# SFP.net
KiCad netlist of a schematic drawn in Altium Designer
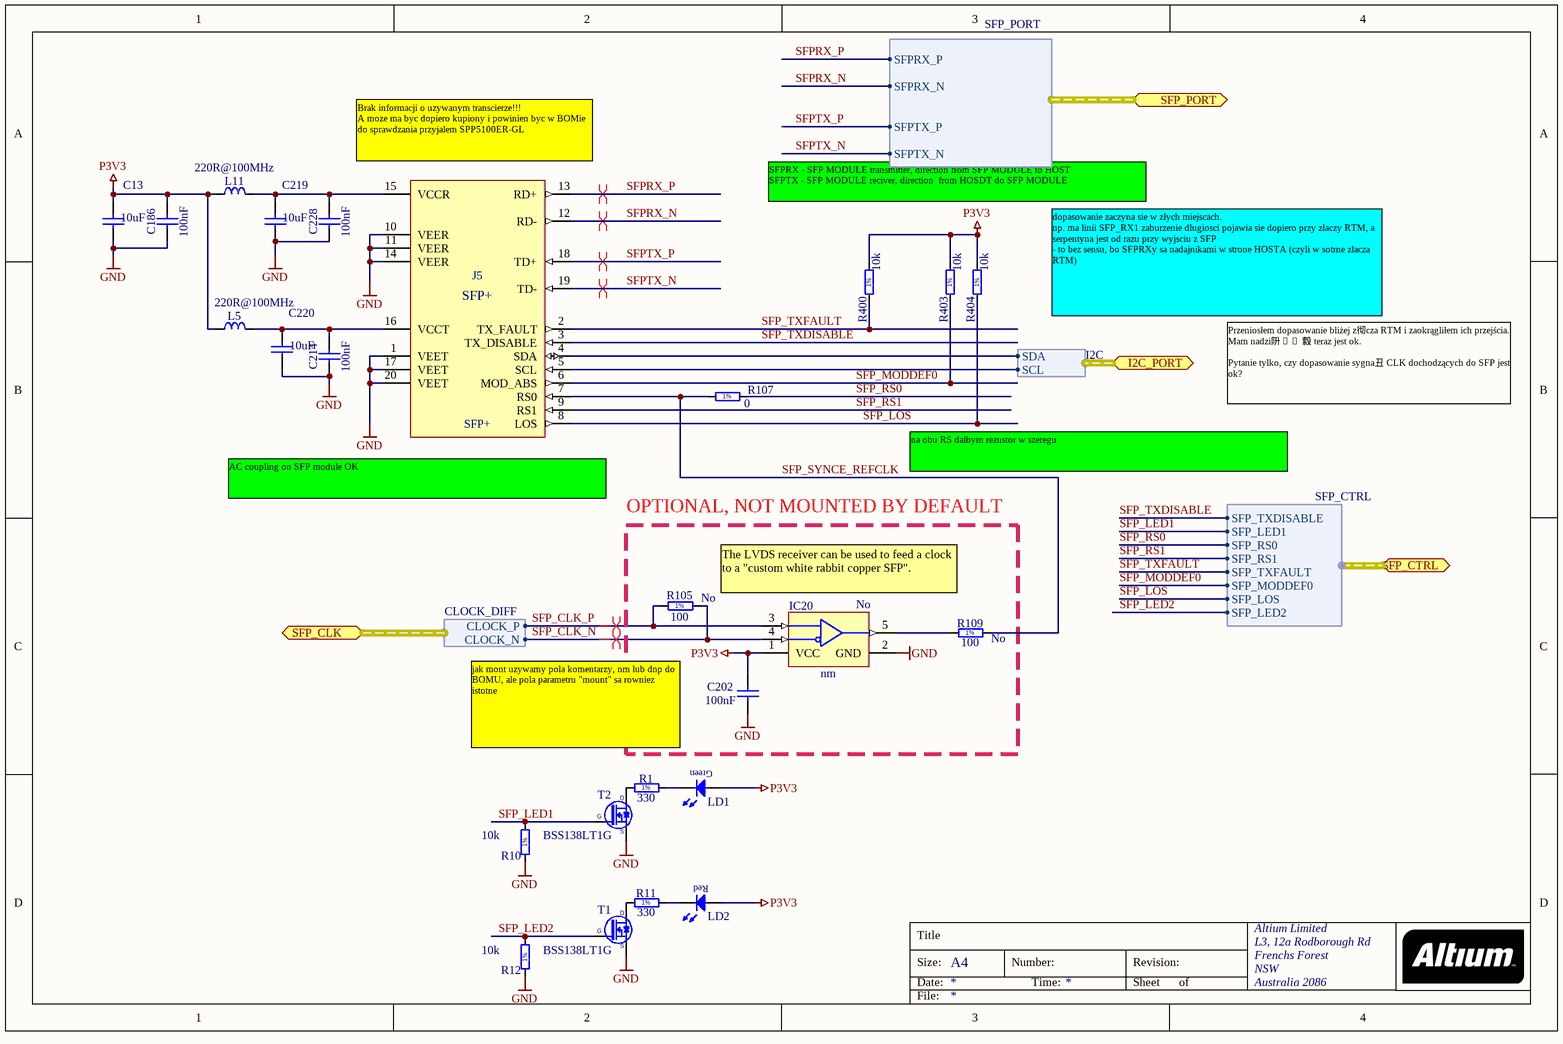
[diagram p0: SFP.SchDoc]

(export (version "E")
  (design (tool "Eeschema 10.0.6"))
  (components
    (comp (ref "C13")
      (value "10uF")
      (footprint "CAPC2012X135N")
      (description "Non-polarised capacitor")
      (fields
        (field (name "PART NUMBER") "CC0805_10UF_10V_10%_X7R")
        (field (name "VOLTAGE") "10V")
        (field (name "AUTHOR") "CERN DEM JLC")
      )
      (libsource (lib "Capacitors") (part "Capacitor - non polarized"))
    )
    (comp (ref "C186")
      (value "100nF")
      (footprint "CAPC1005X55N")
      (description "Non-polarised capacitor")
      (fields
        (field (name "PART NUMBER") "CC0402_100NF_16V_10%_X7R")
        (field (name "VOLTAGE") "16V")
        (field (name "AUTHOR") "CERN DEM JLC")
      )
      (libsource (lib "Capacitors") (part "Capacitor - non polarized"))
    )
    (comp (ref "C202")
      (value "100nF")
      (footprint "CAPC1005X55N")
      (description "Non-polarised capacitor")
      (fields
        (field (name "PART NUMBER") "CC0402_100NF_16V_10%_X7R")
        (field (name "VOLTAGE") "16V")
        (field (name "AUTHOR") "CERN DEM JLC")
      )
      (libsource (lib "Capacitors") (part "Capacitor - non polarized"))
    )
    (comp (ref "C214")
      (value "100nF")
      (footprint "CAPC1005X55N")
      (description "Non-polarised capacitor")
      (fields
        (field (name "PART NUMBER") "CC0402_100NF_16V_10%_X7R")
        (field (name "VOLTAGE") "16V")
        (field (name "AUTHOR") "CERN DEM JLC")
      )
      (libsource (lib "Capacitors") (part "Capacitor - non polarized"))
    )
    (comp (ref "C219")
      (value "10uF")
      (footprint "CAPC2012X135N")
      (description "Non-polarised capacitor")
      (fields
        (field (name "PART NUMBER") "CC0805_10UF_10V_10%_X7R")
        (field (name "VOLTAGE") "10V")
        (field (name "AUTHOR") "CERN DEM JLC")
      )
      (libsource (lib "Capacitors") (part "Capacitor - non polarized"))
    )
    (comp (ref "C220")
      (value "10uF")
      (footprint "CAPC2012X135N")
      (description "Non-polarised capacitor")
      (fields
        (field (name "PART NUMBER") "CC0805_10UF_10V_10%_X7R")
        (field (name "VOLTAGE") "10V")
        (field (name "AUTHOR") "CERN DEM JLC")
      )
      (libsource (lib "Capacitors") (part "Capacitor - non polarized"))
    )
    (comp (ref "C228")
      (value "100nF")
      (footprint "CAPC1005X55N")
      (description "Non-polarised capacitor")
      (fields
        (field (name "PART NUMBER") "CC0402_100NF_16V_10%_X7R")
        (field (name "VOLTAGE") "16V")
        (field (name "AUTHOR") "CERN DEM JLC")
      )
      (libsource (lib "Capacitors") (part "Capacitor - non polarized"))
    )
    (comp (ref "IC20")
      (value "nm")
      (footprint "SOT95P280X145-5N")
      (description "High-Speed Differential Line Receiver")
      (fields
        (field (name "PART NUMBER") "SN65LVDS2DBVR")
        (field (name "MANUFACTURER") "TEXAS INSTRUMENTS")
        (field (name "MOUNTED") "No")
        (field (name "AUTHOR") "CERN DEM JLC")
      )
      (libsource (lib "ICs And Semiconductors") (part "SN65LVDS2DBVR"))
    )
    (comp (ref "J5")
      (value "SFP+")
      (footprint "TYCO_1888247-1")
      (description "20 Position SFP+ Connector (Small Form-factor Pluggable)")
      (fields
        (field (name "PART NUMBER") "TYCO_1888247-1")
        (field (name "MANUFACTURER") "TYCO ELECTRONICS")
        (field (name "AUTHOR") "CERN DEM JLC")
      )
      (libsource (lib "Connectors") (part "SFP+x1"))
    )
    (comp (ref "L5")
      (value "220R@100MHz")
      (footprint "INDC2012X105N")
      (description "Inductor")
      (fields
        (field (name "PART NUMBER") "IND0805_MURATA_BLM21PG221SN1D")
        (field (name "POWER") "2A")
        (field (name "AUTHOR") "CERN DEM JLC")
      )
      (libsource (lib "Inductors & Transformers") (part "Inductor"))
    )
    (comp (ref "L11")
      (value "220R@100MHz")
      (footprint "INDC2012X105N")
      (description "Inductor")
      (fields
        (field (name "PART NUMBER") "IND0805_MURATA_BLM21PG221SN1D")
        (field (name "POWER") "2A")
        (field (name "AUTHOR") "CERN DEM JLC")
      )
      (libsource (lib "Inductors & Transformers") (part "Inductor"))
    )
    (comp (ref "LD1")
      (value "Green")
      (footprint "LED_AVAGO_HSME-C120")
      (description "LED Green Avago C120")
      (fields
        (field (name "PART NUMBER") "LED_AVAGO_HSME-C120")
        (field (name "MANUFACTURER") "AVAGO TECHNOLOGIES")
        (field (name "AUTHOR") "CERN DEM JMW")
      )
      (libsource (lib "LIBRARY_SCH") (part "LED_SMD_90deg_mini_G"))
    )
    (comp (ref "LD2")
      (value "Red")
      (footprint "LED_AVAGO_HSME-C120")
      (description "LED Red Avago C120")
      (fields
        (field (name "PART NUMBER") "LED_AVAGO_HSMC-C120")
        (field (name "MANUFACTURER") "AVAGO TECHNOLOGIES")
        (field (name "AUTHOR") "CERN DEM JMW")
      )
      (libsource (lib "LIBRARY_SCH") (part "LED_SMD_90deg_mini_R"))
    )
    (comp (ref "R1")
      (value "330")
      (footprint "RESC1608X55N")
      (description "Resistor - 1%")
      (fields
        (field (name "PART NUMBER") "R0603_330R_1%_0.1W_100PPM")
        (field (name "POWER") "0.1W")
        (field (name "AUTHOR") "CERN DEM JLC")
      )
      (libsource (lib "Resistors") (part "Resistor - 1%"))
    )
    (comp (ref "R10")
      (value "10k")
      (footprint "RESC1608X55N")
      (description "Resistor - 1%")
      (fields
        (field (name "PART NUMBER") "R0603_10K_1%_0.1W_100PPM")
        (field (name "POWER") "0.1W")
        (field (name "AUTHOR") "CERN DEM JLC")
      )
      (libsource (lib "Resistors") (part "Resistor - 1%"))
    )
    (comp (ref "R11")
      (value "330")
      (footprint "RESC1608X55N")
      (description "Resistor - 1%")
      (fields
        (field (name "PART NUMBER") "R0603_330R_1%_0.1W_100PPM")
        (field (name "POWER") "0.1W")
        (field (name "AUTHOR") "CERN DEM JLC")
      )
      (libsource (lib "Resistors") (part "Resistor - 1%"))
    )
    (comp (ref "R12")
      (value "10k")
      (footprint "RESC1608X55N")
      (description "Resistor - 1%")
      (fields
        (field (name "PART NUMBER") "R0603_10K_1%_0.1W_100PPM")
        (field (name "POWER") "0.1W")
        (field (name "AUTHOR") "CERN DEM JLC")
      )
      (libsource (lib "Resistors") (part "Resistor - 1%"))
    )
    (comp (ref "R105")
      (value "100")
      (footprint "RESC1608X55N")
      (description "Resistor - 1%")
      (fields
        (field (name "PART NUMBER") "R0603_100R_1%_0.1W_100PPM")
        (field (name "POWER") "0.1W")
        (field (name "MOUNTED") "No")
        (field (name "AUTHOR") "CERN DEM JLC")
      )
      (libsource (lib "Resistors") (part "Resistor - 1%"))
    )
    (comp (ref "R107")
      (value "0")
      (footprint "RESC1608X55N")
      (description "Resistor - 1%")
      (fields
        (field (name "PART NUMBER") "R0603_0R_JUMPER")
        (field (name "MANUFACTURER") "GENERIC")
        (field (name "AUTHOR") "CERN DEM JLC")
      )
      (libsource (lib "Resistors") (part "Resistor - 1%"))
    )
    (comp (ref "R109")
      (value "100")
      (footprint "RESC1608X55N")
      (description "Resistor - 1%")
      (fields
        (field (name "PART NUMBER") "R0603_100R_1%_0.1W_100PPM")
        (field (name "POWER") "0.1W")
        (field (name "MOUNTED") "No")
        (field (name "AUTHOR") "CERN DEM JLC")
      )
      (libsource (lib "Resistors") (part "Resistor - 1%"))
    )
    (comp (ref "R400")
      (value "10k")
      (footprint "RESC1608X55N")
      (description "Resistor - 1%")
      (fields
        (field (name "PART NUMBER") "R0603_10K_1%_0.1W_100PPM")
        (field (name "POWER") "0.1W")
        (field (name "AUTHOR") "CERN DEM JLC")
      )
      (libsource (lib "Resistors") (part "Resistor - 1%"))
    )
    (comp (ref "R403")
      (value "10k")
      (footprint "RESC1608X55N")
      (description "Resistor - 1%")
      (fields
        (field (name "PART NUMBER") "R0603_10K_1%_0.1W_100PPM")
        (field (name "POWER") "0.1W")
        (field (name "AUTHOR") "CERN DEM JLC")
      )
      (libsource (lib "Resistors") (part "Resistor - 1%"))
    )
    (comp (ref "R404")
      (value "10k")
      (footprint "RESC1608X55N")
      (description "Resistor - 1%")
      (fields
        (field (name "PART NUMBER") "R0603_10K_1%_0.1W_100PPM")
        (field (name "POWER") "0.1W")
        (field (name "AUTHOR") "CERN DEM JLC")
      )
      (libsource (lib "Resistors") (part "Resistor - 1%"))
    )
    (comp (ref "T1")
      (value "BSS138LT1G")
      (footprint "SOT95P240X110-3N")
      (description "N-CHANNEL MOSFET WITH DIODE")
      (fields (field (name "MANUFACTURER") "ON SEMICONDUCTOR") (field (name "AUTHOR") "CERN DEM JLC"))
      (libsource (lib "ICs And Semiconductors") (part "N-MOSFET-D 1G 2S 3D"))
    )
    (comp (ref "T2")
      (value "BSS138LT1G")
      (footprint "SOT95P240X110-3N")
      (description "N-CHANNEL MOSFET WITH DIODE")
      (fields (field (name "MANUFACTURER") "ON SEMICONDUCTOR") (field (name "AUTHOR") "CERN DEM JLC"))
      (libsource (lib "ICs And Semiconductors") (part "N-MOSFET-D 1G 2S 3D"))
    )
  )
  (nets
    (net (code "5") (name "/SCL") (class "Default")
      (node (ref "J5") (pin "5") (pinfunction "SCL_5") (pintype "input"))
    )
    (net (code "6") (name "/SDA") (class "Default")
      (node (ref "J5") (pin "4") (pinfunction "SDA_4") (pintype "bidirectional"))
    )
    (net (code "7") (name "/SFPRX_N") (class "Default")
      (node (ref "J5") (pin "12") (pinfunction "RD-_12") (pintype "output"))
    )
    (net (code "8") (name "/SFPRX_P") (class "Default")
      (node (ref "J5") (pin "13") (pinfunction "RD+_13") (pintype "output"))
    )
    (net (code "9") (name "/SFPTX_N") (class "Default")
      (node (ref "J5") (pin "19") (pinfunction "TD-_19") (pintype "input"))
    )
    (net (code "10") (name "/SFPTX_P") (class "Default")
      (node (ref "J5") (pin "18") (pinfunction "TD+_18") (pintype "input"))
    )
    (net (code "11") (name "/SFP_CLK_N") (class "Default")
      (node (ref "IC20") (pin "4") (pinfunction "B_4") (pintype "input"))
      (node (ref "R105") (pin "2") (pinfunction "2_2") (pintype "passive"))
    )
    (net (code "12") (name "/SFP_CLK_P") (class "Default")
      (node (ref "IC20") (pin "3") (pinfunction "A_3") (pintype "input"))
      (node (ref "R105") (pin "1") (pinfunction "1_1") (pintype "passive"))
    )
    (net (code "13") (name "/SFP_LED1") (class "Default")
      (node (ref "R10") (pin "2") (pinfunction "2_2") (pintype "passive"))
      (node (ref "T2") (pin "1") (pinfunction "G_1") (pintype "passive"))
    )
    (net (code "14") (name "/SFP_LED2") (class "Default")
      (node (ref "R12") (pin "2") (pinfunction "2_2") (pintype "passive"))
      (node (ref "T1") (pin "1") (pinfunction "G_1") (pintype "passive"))
    )
    (net (code "15") (name "/SFP_LOS") (class "Default")
      (node (ref "J5") (pin "8") (pinfunction "LOS_8") (pintype "output"))
      (node (ref "R404") (pin "1") (pinfunction "1_1") (pintype "passive"))
    )
    (net (code "16") (name "/SFP_MODDEF0") (class "Default")
      (node (ref "J5") (pin "6") (pinfunction "MOD_ABS_6") (pintype "output"))
      (node (ref "R403") (pin "1") (pinfunction "1_1") (pintype "passive"))
    )
    (net (code "17") (name "/SFP_RS0") (class "Default")
      (node (ref "R107") (pin "2") (pinfunction "2_2") (pintype "passive"))
    )
    (net (code "18") (name "/SFP_RS1") (class "Default")
      (node (ref "J5") (pin "9") (pinfunction "RS1_9") (pintype "input"))
    )
    (net (code "19") (name "/SFP_SYNCE_REFCLK") (class "Default")
      (node (ref "J5") (pin "7") (pinfunction "RS0_7") (pintype "input"))
      (node (ref "R107") (pin "1") (pinfunction "1_1") (pintype "passive"))
      (node (ref "R109") (pin "2") (pinfunction "2_2") (pintype "passive"))
    )
    (net (code "20") (name "/SFP_TXDISABLE") (class "Default")
      (node (ref "J5") (pin "3") (pinfunction "TX_DISABLE_3") (pintype "input"))
    )
    (net (code "21") (name "/SFP_TXFAULT") (class "Default")
      (node (ref "J5") (pin "2") (pinfunction "TX_FAULT_2") (pintype "output"))
      (node (ref "R400") (pin "1") (pinfunction "1_1") (pintype "passive"))
    )
    (net (code "26") (name "GND") (class "Default")
      (node (ref "C13") (pin "2") (pinfunction "2_2") (pintype "passive"))
      (node (ref "C186") (pin "2") (pinfunction "2_2") (pintype "passive"))
      (node (ref "C202") (pin "1") (pinfunction "1_1") (pintype "passive"))
      (node (ref "C214") (pin "2") (pinfunction "2_2") (pintype "passive"))
      (node (ref "C219") (pin "2") (pinfunction "2_2") (pintype "passive"))
      (node (ref "C220") (pin "2") (pinfunction "2_2") (pintype "passive"))
      (node (ref "C228") (pin "2") (pinfunction "2_2") (pintype "passive"))
      (node (ref "IC20") (pin "2") (pinfunction "GND_2") (pintype "power_in"))
      (node (ref "J5") (pin "1") (pinfunction "VEET_1") (pintype "power_in"))
      (node (ref "J5") (pin "10") (pinfunction "VEER_10") (pintype "power_in"))
      (node (ref "J5") (pin "11") (pinfunction "VEER_11") (pintype "power_in"))
      (node (ref "J5") (pin "14") (pinfunction "VEER_14") (pintype "power_in"))
      (node (ref "J5") (pin "17") (pinfunction "VEET_17") (pintype "power_in"))
      (node (ref "J5") (pin "20") (pinfunction "VEET_20") (pintype "power_in"))
      (node (ref "R10") (pin "1") (pinfunction "1_1") (pintype "passive"))
      (node (ref "R12") (pin "1") (pinfunction "1_1") (pintype "passive"))
      (node (ref "T1") (pin "2") (pinfunction "S_2") (pintype "passive"))
      (node (ref "T2") (pin "2") (pinfunction "S_2") (pintype "passive"))
    )
    (net (code "27") (name "Net-(IC20-R)") (class "Default")
      (node (ref "IC20") (pin "5") (pinfunction "R_5") (pintype "output"))
      (node (ref "R109") (pin "1") (pinfunction "1_1") (pintype "passive"))
    )
    (net (code "28") (name "Net-(J5-VCCR)") (class "Default")
      (node (ref "C219") (pin "1") (pinfunction "1_1") (pintype "passive"))
      (node (ref "C228") (pin "1") (pinfunction "1_1") (pintype "passive"))
      (node (ref "J5") (pin "15") (pinfunction "VCCR_15") (pintype "power_in"))
      (node (ref "L11") (pin "2") (pinfunction "2_2") (pintype "passive"))
    )
    (net (code "29") (name "Net-(J5-VCCT)") (class "Default")
      (node (ref "C214") (pin "1") (pinfunction "1_1") (pintype "passive"))
      (node (ref "C220") (pin "1") (pinfunction "1_1") (pintype "passive"))
      (node (ref "J5") (pin "16") (pinfunction "VCCT_16") (pintype "power_in"))
      (node (ref "L5") (pin "2") (pinfunction "2_2") (pintype "passive"))
    )
    (net (code "30") (name "Net-(LD1-C)") (class "Default")
      (node (ref "LD1") (pin "2") (pinfunction "C_2") (pintype "passive"))
      (node (ref "R1") (pin "2") (pinfunction "2_2") (pintype "passive"))
    )
    (net (code "31") (name "Net-(LD2-C)") (class "Default")
      (node (ref "LD2") (pin "2") (pinfunction "C_2") (pintype "passive"))
      (node (ref "R11") (pin "2") (pinfunction "2_2") (pintype "passive"))
    )
    (net (code "32") (name "Net-(T1-D)") (class "Default")
      (node (ref "R11") (pin "1") (pinfunction "1_1") (pintype "passive"))
      (node (ref "T1") (pin "3") (pinfunction "D_3") (pintype "passive"))
    )
    (net (code "33") (name "Net-(T2-D)") (class "Default")
      (node (ref "R1") (pin "1") (pinfunction "1_1") (pintype "passive"))
      (node (ref "T2") (pin "3") (pinfunction "D_3") (pintype "passive"))
    )
    (net (code "34") (name "P3V3") (class "Default")
      (node (ref "C13") (pin "1") (pinfunction "1_1") (pintype "passive"))
      (node (ref "C186") (pin "1") (pinfunction "1_1") (pintype "passive"))
      (node (ref "C202") (pin "2") (pinfunction "2_2") (pintype "passive"))
      (node (ref "IC20") (pin "1") (pinfunction "VCC_1") (pintype "power_in"))
      (node (ref "L11") (pin "1") (pinfunction "1_1") (pintype "passive"))
      (node (ref "L5") (pin "1") (pinfunction "1_1") (pintype "passive"))
      (node (ref "LD1") (pin "1") (pinfunction "A_1") (pintype "passive"))
      (node (ref "LD2") (pin "1") (pinfunction "A_1") (pintype "passive"))
      (node (ref "R400") (pin "2") (pinfunction "2_2") (pintype "passive"))
      (node (ref "R403") (pin "2") (pinfunction "2_2") (pintype "passive"))
      (node (ref "R404") (pin "2") (pinfunction "2_2") (pintype "passive"))
    )
  )
)
